# gpi-filter0.net
KiCad netlist of a schematic drawn in EAGLE
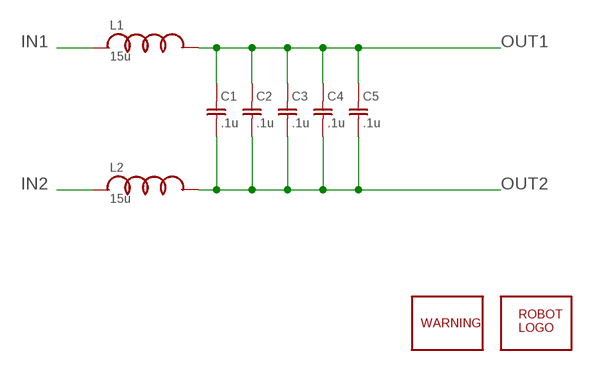
[diagram p0: schematic, sheet 1]

(export (version "E")
  (design (tool "Eeschema 10.0.6"))
  (components
    (comp (ref "C1")
      (value ".1u")
      (footprint "eagle-import:SMD1210")
      (libsource (lib "eagle-import") (part "C1210"))
    )
    (comp (ref "C2")
      (value ".1u")
      (footprint "eagle-import:SMD1210")
      (libsource (lib "eagle-import") (part "C1210"))
    )
    (comp (ref "C3")
      (value ".1u")
      (footprint "eagle-import:SMD1210")
      (libsource (lib "eagle-import") (part "C1210"))
    )
    (comp (ref "C4")
      (value ".1u")
      (footprint "eagle-import:SMD1210")
      (libsource (lib "eagle-import") (part "C1210"))
    )
    (comp (ref "C5")
      (value ".1u")
      (footprint "eagle-import:SMD1210")
      (libsource (lib "eagle-import") (part "C1210"))
    )
    (comp (ref "L1")
      (value "15u")
      (footprint "eagle-import:BOURNS2303H")
      (libsource (lib "eagle-import") (part "L"))
    )
    (comp (ref "L2")
      (value "15u")
      (footprint "eagle-import:BOURNS2303H")
      (libsource (lib "eagle-import") (part "L"))
    )
    (comp (ref "U$1")
      (value "ROBOTMAN-LOGO")
      (footprint "eagle-import:ROBOTMAN-LOGO")
      (libsource (lib "eagle-import") (part "ROBOTMAN-LOGO"))
    )
    (comp (ref "U$2")
      (value "SYMBOL-WARNING")
      (footprint "eagle-import:SYMBOL-WARNING")
      (libsource (lib "eagle-import") (part "SYMBOL-WARNING"))
    )
  )
  (nets
    (net (code "1") (name "/IN1") (class "Default")
      (node (ref "L1") (pin "P$1") (pinfunction "P$1_P$1") (pintype "passive"))
    )
    (net (code "2") (name "/IN2") (class "Default")
      (node (ref "L2") (pin "P$1") (pinfunction "P$1_P$1") (pintype "passive"))
    )
    (net (code "3") (name "/OUT1") (class "Default")
      (node (ref "C1") (pin "1") (pinfunction "P$1_1") (pintype "passive"))
      (node (ref "C2") (pin "1") (pinfunction "P$1_1") (pintype "passive"))
      (node (ref "C3") (pin "1") (pinfunction "P$1_1") (pintype "passive"))
      (node (ref "C4") (pin "1") (pinfunction "P$1_1") (pintype "passive"))
      (node (ref "C5") (pin "1") (pinfunction "P$1_1") (pintype "passive"))
      (node (ref "L1") (pin "P$2") (pinfunction "P$2_P$2") (pintype "passive"))
    )
    (net (code "4") (name "/OUT2") (class "Default")
      (node (ref "C1") (pin "2") (pinfunction "P$2_2") (pintype "passive"))
      (node (ref "C2") (pin "2") (pinfunction "P$2_2") (pintype "passive"))
      (node (ref "C3") (pin "2") (pinfunction "P$2_2") (pintype "passive"))
      (node (ref "C4") (pin "2") (pinfunction "P$2_2") (pintype "passive"))
      (node (ref "C5") (pin "2") (pinfunction "P$2_2") (pintype "passive"))
      (node (ref "L2") (pin "P$2") (pinfunction "P$2_P$2") (pintype "passive"))
    )
  )
)
